# vfd_drive.net
KiCad netlist of a schematic drawn in EAGLE
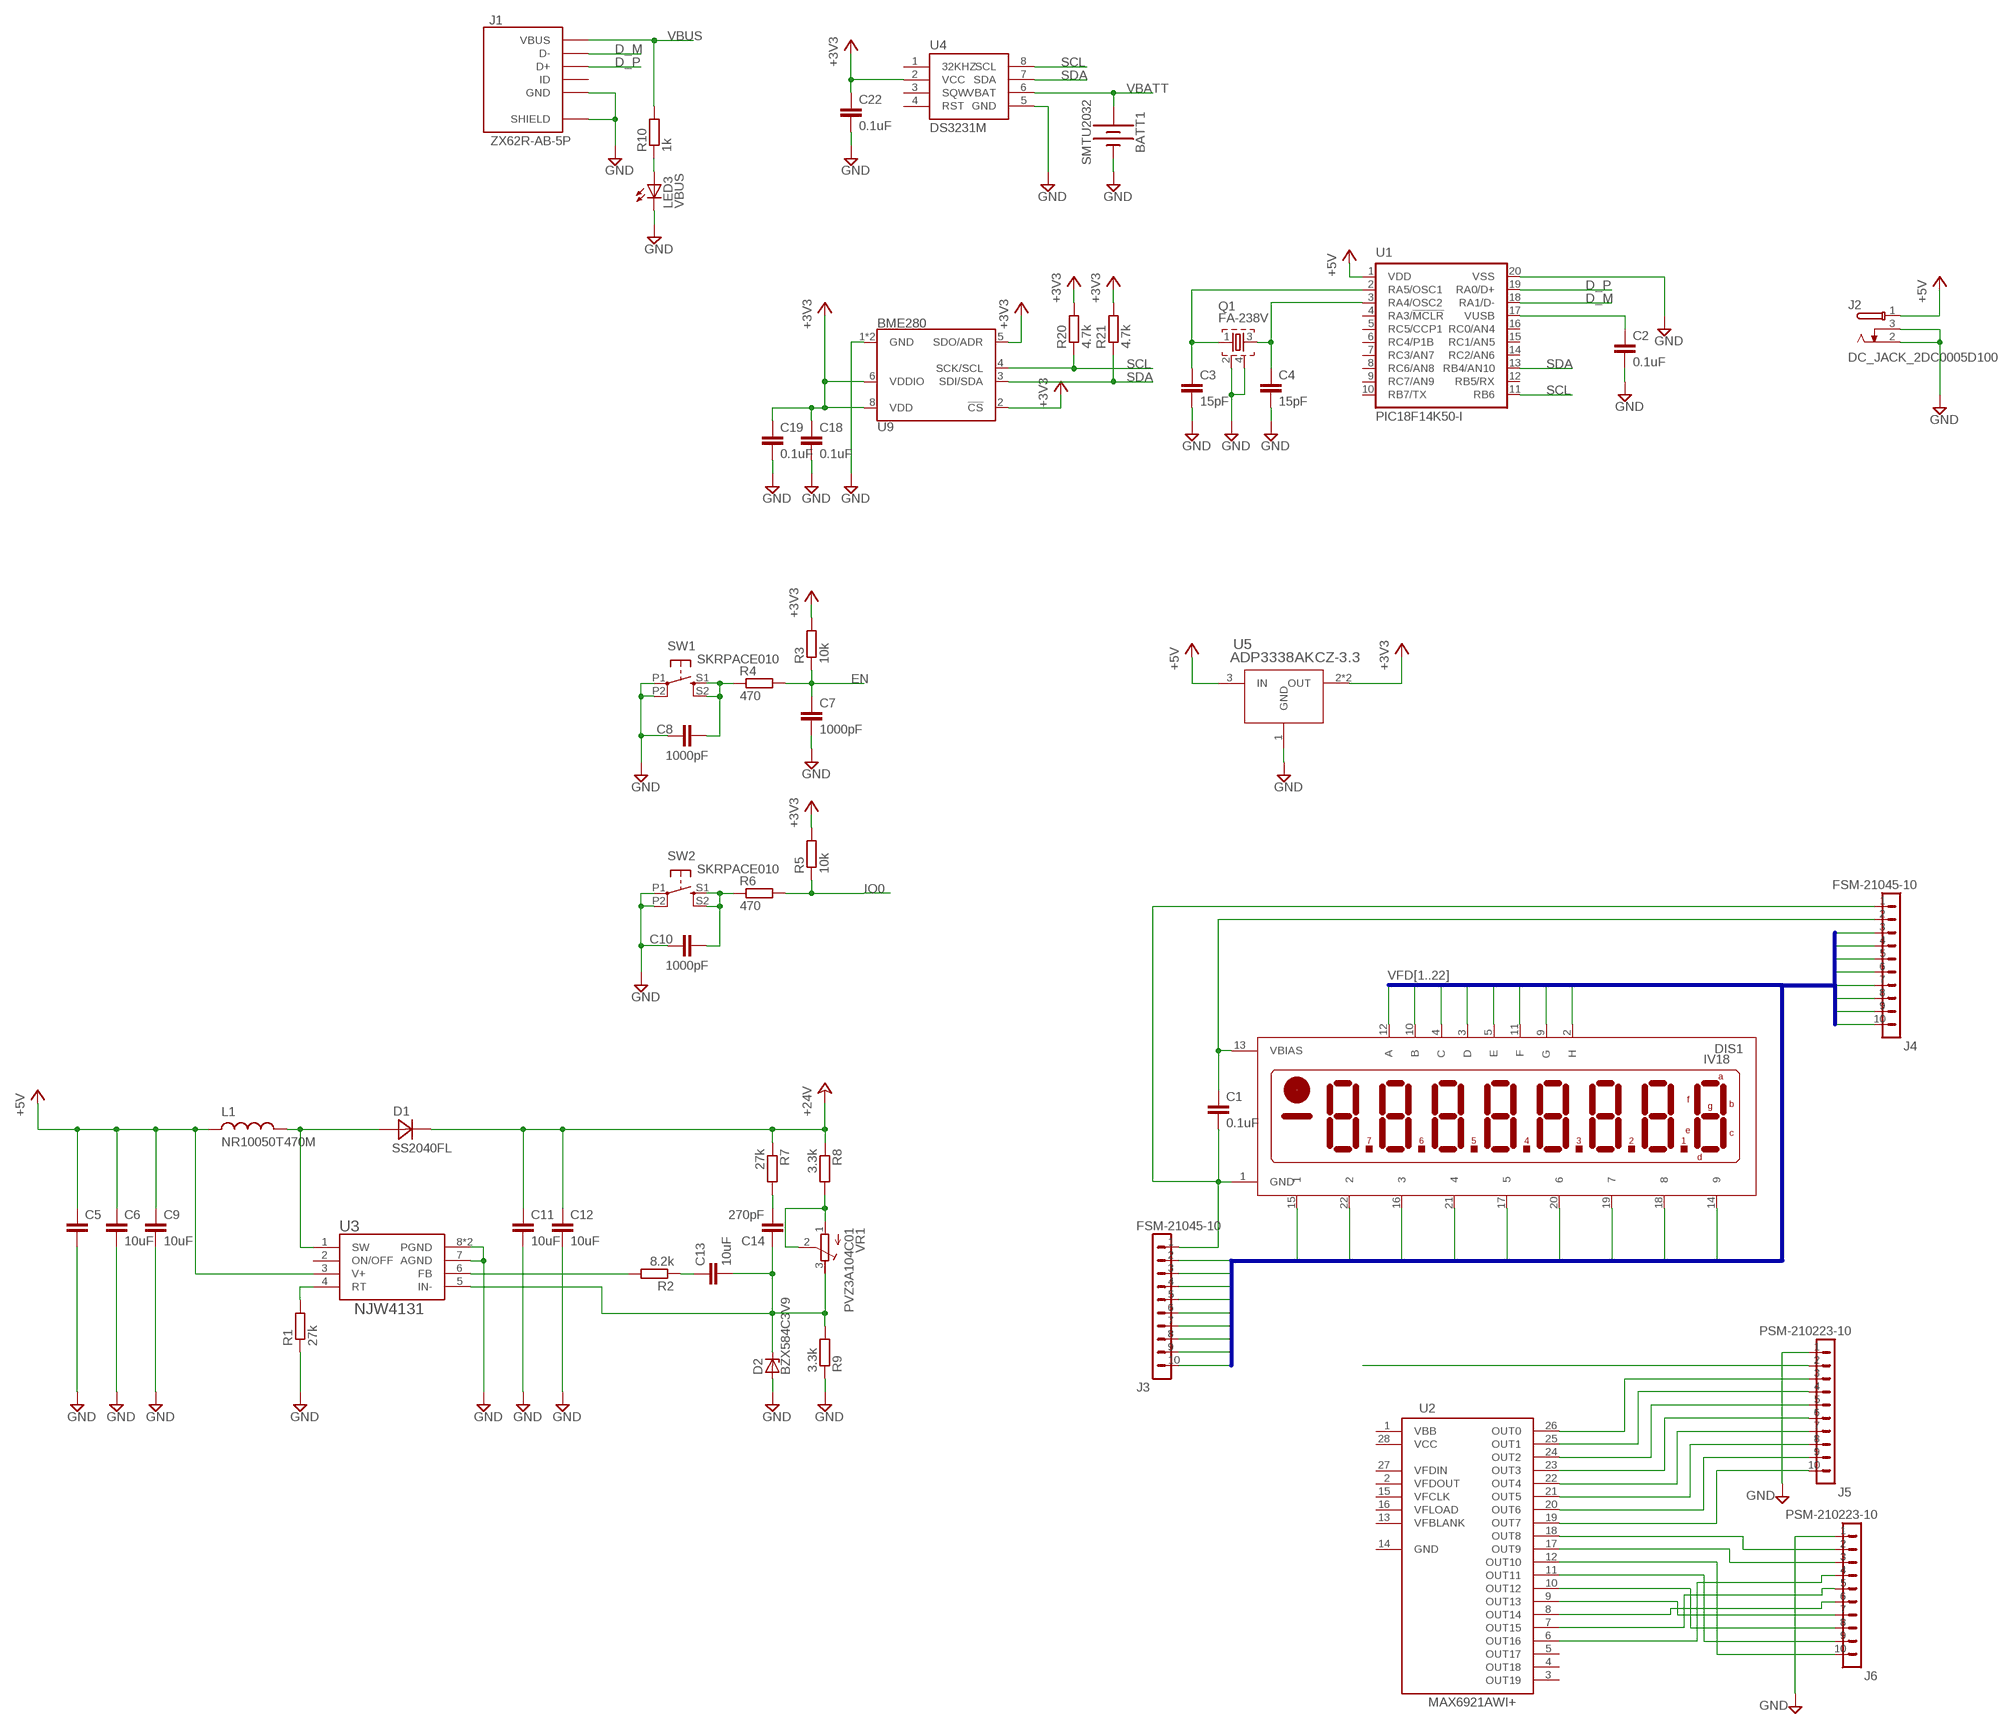
[diagram p0: schematic, sheet 1]

(export (version "E")
  (design (tool "Eeschema 10.0.6"))
  (components
    (comp (ref "BATT1")
      (value "SMTU2032")
      (footprint "eagle-import:SMTU2032")
      (libsource (lib "eagle-import") (part "SMTU2032"))
    )
    (comp (ref "C1")
      (value "0.1uF")
      (footprint "eagle-import:C0603")
      (libsource (lib "eagle-import") (part "C-EUC0603"))
    )
    (comp (ref "C2")
      (value "0.1uF")
      (footprint "eagle-import:C0603")
      (libsource (lib "eagle-import") (part "C-EUC0603"))
    )
    (comp (ref "C3")
      (value "15pF")
      (footprint "eagle-import:C0603")
      (libsource (lib "eagle-import") (part "C-EUC0603"))
    )
    (comp (ref "C4")
      (value "15pF")
      (footprint "eagle-import:C0603")
      (libsource (lib "eagle-import") (part "C-EUC0603"))
    )
    (comp (ref "C5")
      (value "C-EUC3225")
      (footprint "eagle-import:C3225")
      (libsource (lib "eagle-import") (part "C-EUC3225"))
    )
    (comp (ref "C6")
      (value "10uF")
      (footprint "eagle-import:C0603")
      (libsource (lib "eagle-import") (part "C-EUC0603"))
    )
    (comp (ref "C7")
      (value "1000pF")
      (footprint "eagle-import:C0603")
      (libsource (lib "eagle-import") (part "C-EUC0603"))
    )
    (comp (ref "C8")
      (value "1000pF")
      (footprint "eagle-import:C0603")
      (libsource (lib "eagle-import") (part "C-EUC0603"))
    )
    (comp (ref "C9")
      (value "10uF")
      (footprint "eagle-import:C0603")
      (libsource (lib "eagle-import") (part "C-EUC0603"))
    )
    (comp (ref "C10")
      (value "1000pF")
      (footprint "eagle-import:C0603")
      (libsource (lib "eagle-import") (part "C-EUC0603"))
    )
    (comp (ref "C11")
      (value "10uF")
      (footprint "eagle-import:C3216")
      (libsource (lib "eagle-import") (part "C-EUC3216"))
    )
    (comp (ref "C12")
      (value "10uF")
      (footprint "eagle-import:C3216")
      (libsource (lib "eagle-import") (part "C-EUC3216"))
    )
    (comp (ref "C13")
      (value "10uF")
      (footprint "eagle-import:C0603")
      (libsource (lib "eagle-import") (part "C-EUC0603"))
    )
    (comp (ref "C14")
      (value "270pF")
      (footprint "eagle-import:C0603")
      (libsource (lib "eagle-import") (part "C-EUC0603"))
    )
    (comp (ref "C18")
      (value "0.1uF")
      (footprint "eagle-import:C0603")
      (libsource (lib "eagle-import") (part "C-EUC0603"))
    )
    (comp (ref "C19")
      (value "0.1uF")
      (footprint "eagle-import:C0603")
      (libsource (lib "eagle-import") (part "C-EUC0603"))
    )
    (comp (ref "C22")
      (value "0.1uF")
      (footprint "eagle-import:C0603")
      (libsource (lib "eagle-import") (part "C-EUC0603"))
    )
    (comp (ref "D1")
      (value "SS2040FL")
      (footprint "eagle-import:SOD-123FL")
      (libsource (lib "eagle-import") (part "SS2040FL"))
    )
    (comp (ref "D2")
      (value "BZX584C3V9")
      (footprint "eagle-import:SOD-523")
      (libsource (lib "eagle-import") (part "BZX584C3V9"))
    )
    (comp (ref "DIS1")
      (value "IV18")
      (footprint "eagle-import:IV18")
      (libsource (lib "eagle-import") (part "IV18"))
    )
    (comp (ref "J1")
      (value "ZX62R-AB-5P")
      (footprint "eagle-import:ZX62R-B-5PA")
      (libsource (lib "eagle-import") (part "ZX62R-AB-5P"))
    )
    (comp (ref "J2")
      (value "DC_JACK_2DC0005D100")
      (footprint "eagle-import:DC_JACK_2DC0005D100")
      (libsource (lib "eagle-import") (part "DC_JACK_2DC0005D100"))
    )
    (comp (ref "J3")
      (value "FSM-21045-10")
      (footprint "eagle-import:FSM-21045-10")
      (libsource (lib "eagle-import") (part "FSM-21045-10"))
    )
    (comp (ref "J4")
      (value "FSM-21045-10")
      (footprint "eagle-import:FSM-21045-10")
      (libsource (lib "eagle-import") (part "FSM-21045-10"))
    )
    (comp (ref "J5")
      (value "PSM-210223-10")
      (footprint "eagle-import:PSM-210223-10")
      (libsource (lib "eagle-import") (part "PSM-210223-10"))
    )
    (comp (ref "J6")
      (value "PSM-210223-10")
      (footprint "eagle-import:PSM-210223-10")
      (libsource (lib "eagle-import") (part "PSM-210223-10"))
    )
    (comp (ref "L1")
      (value "NR10050T470M")
      (footprint "eagle-import:NR10050T100M")
      (libsource (lib "eagle-import") (part "NR10050T470M"))
    )
    (comp (ref "LED3")
      (value "VBUS")
      (footprint "eagle-import:CHIPLED_0603")
      (libsource (lib "eagle-import") (part "LEDCHIPLED_0603"))
    )
    (comp (ref "Q1")
      (value "FA-238V")
      (footprint "eagle-import:FA238-V")
      (libsource (lib "eagle-import") (part "FA-238V"))
    )
    (comp (ref "R1")
      (value "27k")
      (footprint "eagle-import:R0603")
      (libsource (lib "eagle-import") (part "R-EU_R0603"))
    )
    (comp (ref "R2")
      (value "8.2k")
      (footprint "eagle-import:R0603")
      (libsource (lib "eagle-import") (part "R-EU_R0603"))
    )
    (comp (ref "R3")
      (value "10k")
      (footprint "eagle-import:R0603")
      (libsource (lib "eagle-import") (part "R-EU_R0603"))
    )
    (comp (ref "R4")
      (value "470")
      (footprint "eagle-import:R0603")
      (libsource (lib "eagle-import") (part "R-EU_R0603"))
    )
    (comp (ref "R5")
      (value "10k")
      (footprint "eagle-import:R0603")
      (libsource (lib "eagle-import") (part "R-EU_R0603"))
    )
    (comp (ref "R6")
      (value "470")
      (footprint "eagle-import:R0603")
      (libsource (lib "eagle-import") (part "R-EU_R0603"))
    )
    (comp (ref "R7")
      (value "27k")
      (footprint "eagle-import:R0603")
      (libsource (lib "eagle-import") (part "R-EU_R0603"))
    )
    (comp (ref "R8")
      (value "3.3k")
      (footprint "eagle-import:R0603")
      (libsource (lib "eagle-import") (part "R-EU_R0603"))
    )
    (comp (ref "R9")
      (value "3.3k")
      (footprint "eagle-import:R0603")
      (libsource (lib "eagle-import") (part "R-EU_R0603"))
    )
    (comp (ref "R10")
      (value "1k")
      (footprint "eagle-import:R0603")
      (libsource (lib "eagle-import") (part "R-EU_R0603"))
    )
    (comp (ref "R20")
      (value "4.7k")
      (footprint "eagle-import:R0603")
      (libsource (lib "eagle-import") (part "R-EU_R0603"))
    )
    (comp (ref "R21")
      (value "4.7k")
      (footprint "eagle-import:R0603")
      (libsource (lib "eagle-import") (part "R-EU_R0603"))
    )
    (comp (ref "SW1")
      (value "SKRPACE010")
      (footprint "eagle-import:SKRPACE010")
      (libsource (lib "eagle-import") (part "SKRPACE010"))
    )
    (comp (ref "SW2")
      (value "SKRPACE010")
      (footprint "eagle-import:SKRPACE010")
      (libsource (lib "eagle-import") (part "SKRPACE010"))
    )
    (comp (ref "U1")
      (value "PIC18F14K50-I")
      (footprint "eagle-import:SSOP20")
      (libsource (lib "eagle-import") (part "PIC18F14K50-I"))
    )
    (comp (ref "U2")
      (value "MAX6921AWI+")
      (footprint "eagle-import:SOIC-28-MI")
      (libsource (lib "eagle-import") (part "MAX6921AWI+"))
    )
    (comp (ref "U3")
      (value "NJW4131")
      (footprint "eagle-import:HSOP8")
      (libsource (lib "eagle-import") (part "NJW4131"))
    )
    (comp (ref "U4")
      (value "DS3231M")
      (footprint "eagle-import:SO08")
      (libsource (lib "eagle-import") (part "DS3231M"))
    )
    (comp (ref "U5")
      (value "ADP3338AKCZ-3.3")
      (footprint "eagle-import:SOT233")
      (libsource (lib "eagle-import") (part "ADP3338AKCZ-3.3"))
    )
    (comp (ref "U9")
      (value "BME280")
      (footprint "eagle-import:LGA-8-2.5X2.5")
      (libsource (lib "eagle-import") (part "BME280"))
    )
    (comp (ref "VR1")
      (value "PVZ3A104C01")
      (footprint "eagle-import:PVZ3A")
      (libsource (lib "eagle-import") (part "PVZ3A104C01"))
    )
  )
  (nets
    (net (code "6") (name "+3V3") (class "Default")
      (node (ref "C18") (pin "1") (pinfunction "1_1") (pintype "passive"))
      (node (ref "C19") (pin "1") (pinfunction "1_1") (pintype "passive"))
      (node (ref "C22") (pin "1") (pinfunction "1_1") (pintype "passive"))
      (node (ref "R20") (pin "2") (pinfunction "2_2") (pintype "passive"))
      (node (ref "R21") (pin "2") (pinfunction "2_2") (pintype "passive"))
      (node (ref "R3") (pin "2") (pinfunction "2_2") (pintype "passive"))
      (node (ref "R5") (pin "2") (pinfunction "2_2") (pintype "passive"))
      (node (ref "U4") (pin "2") (pinfunction "VCC_2") (pintype "power_in"))
      (node (ref "U5") (pin "2") (pinfunction "OUT_2") (pintype "passive"))
      (node (ref "U5") (pin "4") (pinfunction "OUT_4") (pintype "passive"))
      (node (ref "U9") (pin "2") (pinfunction "~{CS}_2") (pintype "bidirectional"))
      (node (ref "U9") (pin "5") (pinfunction "SDO/ADR_5") (pintype "bidirectional"))
      (node (ref "U9") (pin "6") (pinfunction "VDDIO_6") (pintype "bidirectional"))
      (node (ref "U9") (pin "8") (pinfunction "VDD_8") (pintype "bidirectional"))
    )
    (net (code "7") (name "+5V") (class "Default")
      (node (ref "C5") (pin "1") (pinfunction "1_1") (pintype "passive"))
      (node (ref "C6") (pin "1") (pinfunction "1_1") (pintype "passive"))
      (node (ref "C9") (pin "1") (pinfunction "1_1") (pintype "passive"))
      (node (ref "J2") (pin "1") (pinfunction "1_1") (pintype "passive"))
      (node (ref "L1") (pin "P$1") (pinfunction "1_P$1") (pintype "passive"))
      (node (ref "U1") (pin "1") (pinfunction "VDD_1") (pintype "power_in"))
      (node (ref "U3") (pin "3") (pinfunction "V+_3") (pintype "bidirectional"))
      (node (ref "U5") (pin "3") (pinfunction "IN_3") (pintype "passive"))
    )
    (net (code "8") (name "+24V") (class "Default")
      (node (ref "C11") (pin "1") (pinfunction "1_1") (pintype "passive"))
      (node (ref "C12") (pin "1") (pinfunction "1_1") (pintype "passive"))
      (node (ref "D1") (pin "K") (pinfunction "C_K") (pintype "passive"))
      (node (ref "R7") (pin "1") (pinfunction "1_1") (pintype "passive"))
      (node (ref "R8") (pin "1") (pinfunction "1_1") (pintype "passive"))
    )
    (net (code "9") (name "/D_M") (class "Default")
      (node (ref "J1") (pin "D-") (pinfunction "D-_D-") (pintype "bidirectional"))
      (node (ref "U1") (pin "18") (pinfunction "RA1/D-_18") (pintype "bidirectional"))
    )
    (net (code "10") (name "/D_P") (class "Default")
      (node (ref "J1") (pin "D+") (pinfunction "D+_D+") (pintype "bidirectional"))
      (node (ref "U1") (pin "19") (pinfunction "RA0/D+_19") (pintype "bidirectional"))
    )
    (net (code "11") (name "/EN") (class "Default")
      (node (ref "C7") (pin "1") (pinfunction "1_1") (pintype "passive"))
      (node (ref "R3") (pin "1") (pinfunction "1_1") (pintype "passive"))
      (node (ref "R4") (pin "2") (pinfunction "2_2") (pintype "passive"))
    )
    (net (code "12") (name "/IO0") (class "Default")
      (node (ref "R5") (pin "1") (pinfunction "1_1") (pintype "passive"))
      (node (ref "R6") (pin "2") (pinfunction "2_2") (pintype "passive"))
    )
    (net (code "13") (name "/SCL") (class "Default")
      (node (ref "R20") (pin "1") (pinfunction "1_1") (pintype "passive"))
      (node (ref "U1") (pin "11") (pinfunction "RB6_11") (pintype "bidirectional"))
      (node (ref "U4") (pin "8") (pinfunction "SCL_8") (pintype "bidirectional"))
      (node (ref "U9") (pin "4") (pinfunction "SCK/SCL_4") (pintype "bidirectional"))
    )
    (net (code "14") (name "/SDA") (class "Default")
      (node (ref "R21") (pin "1") (pinfunction "1_1") (pintype "passive"))
      (node (ref "U1") (pin "13") (pinfunction "RB4/AN10_13") (pintype "bidirectional"))
      (node (ref "U4") (pin "7") (pinfunction "SDA_7") (pintype "bidirectional"))
      (node (ref "U9") (pin "3") (pinfunction "SDI/SDA_3") (pintype "bidirectional"))
    )
    (net (code "15") (name "/VBATT") (class "Default")
      (node (ref "BATT1") (pin "P") (pinfunction "+_P") (pintype "power_in"))
      (node (ref "U4") (pin "6") (pinfunction "VBAT_6") (pintype "power_in"))
    )
    (net (code "16") (name "/VBUS") (class "Default")
      (node (ref "J1") (pin "VCC") (pinfunction "VBUS_VCC") (pintype "bidirectional"))
      (node (ref "R10") (pin "2") (pinfunction "2_2") (pintype "passive"))
    )
    (net (code "17") (name "/VFD2") (class "Default")
      (node (ref "DIS1") (pin "2") (pinfunction "H_2") (pintype "passive"))
      (node (ref "J3") (pin "5") (pinfunction "5_5") (pintype "bidirectional"))
    )
    (net (code "18") (name "/VFD3") (class "Default")
      (node (ref "DIS1") (pin "3") (pinfunction "D_3") (pintype "passive"))
      (node (ref "J3") (pin "4") (pinfunction "4_4") (pintype "bidirectional"))
    )
    (net (code "19") (name "/VFD4") (class "Default")
      (node (ref "DIS1") (pin "4") (pinfunction "C_4") (pintype "passive"))
      (node (ref "J3") (pin "3") (pinfunction "3_3") (pintype "bidirectional"))
    )
    (net (code "20") (name "/VFD5") (class "Default")
      (node (ref "DIS1") (pin "5") (pinfunction "E_5") (pintype "passive"))
      (node (ref "J3") (pin "2") (pinfunction "2_2") (pintype "bidirectional"))
    )
    (net (code "21") (name "/VFD9") (class "Default")
      (node (ref "DIS1") (pin "9") (pinfunction "G_9") (pintype "passive"))
      (node (ref "J4") (pin "3") (pinfunction "3_3") (pintype "bidirectional"))
    )
    (net (code "22") (name "/VFD10") (class "Default")
      (node (ref "DIS1") (pin "10") (pinfunction "B_10") (pintype "passive"))
      (node (ref "J4") (pin "4") (pinfunction "4_4") (pintype "bidirectional"))
    )
    (net (code "23") (name "/VFD11") (class "Default")
      (node (ref "DIS1") (pin "11") (pinfunction "F_11") (pintype "passive"))
      (node (ref "J4") (pin "5") (pinfunction "5_5") (pintype "bidirectional"))
    )
    (net (code "24") (name "/VFD12") (class "Default")
      (node (ref "DIS1") (pin "12") (pinfunction "A_12") (pintype "passive"))
      (node (ref "J4") (pin "6") (pinfunction "6_6") (pintype "bidirectional"))
    )
    (net (code "25") (name "/VFD14") (class "Default")
      (node (ref "DIS1") (pin "14") (pinfunction "9_14") (pintype "passive"))
      (node (ref "J4") (pin "7") (pinfunction "7_7") (pintype "bidirectional"))
    )
    (net (code "26") (name "/VFD15") (class "Default")
      (node (ref "DIS1") (pin "15") (pinfunction "1_15") (pintype "passive"))
      (node (ref "J4") (pin "8") (pinfunction "8_8") (pintype "bidirectional"))
    )
    (net (code "27") (name "/VFD16") (class "Default")
      (node (ref "DIS1") (pin "16") (pinfunction "3_16") (pintype "passive"))
      (node (ref "J4") (pin "9") (pinfunction "9_9") (pintype "bidirectional"))
    )
    (net (code "28") (name "/VFD17") (class "Default")
      (node (ref "DIS1") (pin "17") (pinfunction "5_17") (pintype "passive"))
      (node (ref "J4") (pin "10") (pinfunction "10_10") (pintype "bidirectional"))
    )
    (net (code "29") (name "/VFD18") (class "Default")
      (node (ref "DIS1") (pin "18") (pinfunction "8_18") (pintype "passive"))
      (node (ref "J3") (pin "10") (pinfunction "10_10") (pintype "bidirectional"))
    )
    (net (code "30") (name "/VFD19") (class "Default")
      (node (ref "DIS1") (pin "19") (pinfunction "7_19") (pintype "passive"))
      (node (ref "J3") (pin "9") (pinfunction "9_9") (pintype "bidirectional"))
    )
    (net (code "31") (name "/VFD20") (class "Default")
      (node (ref "DIS1") (pin "20") (pinfunction "6_20") (pintype "passive"))
      (node (ref "J3") (pin "8") (pinfunction "8_8") (pintype "bidirectional"))
    )
    (net (code "32") (name "/VFD21") (class "Default")
      (node (ref "DIS1") (pin "21") (pinfunction "4_21") (pintype "passive"))
      (node (ref "J3") (pin "7") (pinfunction "7_7") (pintype "bidirectional"))
    )
    (net (code "33") (name "/VFD22") (class "Default")
      (node (ref "DIS1") (pin "22") (pinfunction "2_22") (pintype "passive"))
      (node (ref "J3") (pin "6") (pinfunction "6_6") (pintype "bidirectional"))
    )
    (net (code "35") (name "GND") (class "Default")
      (node (ref "BATT1") (pin "N") (pinfunction "-_N") (pintype "power_in"))
      (node (ref "C1") (pin "2") (pinfunction "2_2") (pintype "passive"))
      (node (ref "C10") (pin "1") (pinfunction "1_1") (pintype "passive"))
      (node (ref "C11") (pin "2") (pinfunction "2_2") (pintype "passive"))
      (node (ref "C12") (pin "2") (pinfunction "2_2") (pintype "passive"))
      (node (ref "C18") (pin "2") (pinfunction "2_2") (pintype "passive"))
      (node (ref "C19") (pin "2") (pinfunction "2_2") (pintype "passive"))
      (node (ref "C2") (pin "2") (pinfunction "2_2") (pintype "passive"))
      (node (ref "C22") (pin "2") (pinfunction "2_2") (pintype "passive"))
      (node (ref "C3") (pin "2") (pinfunction "2_2") (pintype "passive"))
      (node (ref "C4") (pin "2") (pinfunction "2_2") (pintype "passive"))
      (node (ref "C5") (pin "2") (pinfunction "2_2") (pintype "passive"))
      (node (ref "C6") (pin "2") (pinfunction "2_2") (pintype "passive"))
      (node (ref "C7") (pin "2") (pinfunction "2_2") (pintype "passive"))
      (node (ref "C8") (pin "1") (pinfunction "1_1") (pintype "passive"))
      (node (ref "C9") (pin "2") (pinfunction "2_2") (pintype "passive"))
      (node (ref "D2") (pin "A") (pinfunction "A_A") (pintype "passive"))
      (node (ref "DIS1") (pin "1") (pinfunction "GND_1") (pintype "power_in"))
      (node (ref "J1") (pin "GND") (pinfunction "GND_GND") (pintype "bidirectional"))
      (node (ref "J1") (pin "SHIELD@1") (pinfunction "SHIELD_SHIELD@1") (pintype "bidirectional"))
      (node (ref "J1") (pin "SHIELD@2") (pinfunction "SHIELD_SHIELD@2") (pintype "bidirectional"))
      (node (ref "J1") (pin "SHIELD@3") (pinfunction "SHIELD_SHIELD@3") (pintype "bidirectional"))
      (node (ref "J1") (pin "SHIELD@4") (pinfunction "SHIELD_SHIELD@4") (pintype "bidirectional"))
      (node (ref "J2") (pin "2") (pinfunction "2_2") (pintype "passive"))
      (node (ref "J2") (pin "3") (pinfunction "3_3") (pintype "passive"))
      (node (ref "J3") (pin "1") (pinfunction "1_1") (pintype "bidirectional"))
      (node (ref "J4") (pin "1") (pinfunction "1_1") (pintype "bidirectional"))
      (node (ref "J5") (pin "1") (pinfunction "1_1") (pintype "bidirectional"))
      (node (ref "J6") (pin "1") (pinfunction "1_1") (pintype "bidirectional"))
      (node (ref "LED3") (pin "C") (pinfunction "C_C") (pintype "passive"))
      (node (ref "Q1") (pin "2") (pinfunction "2_2") (pintype "passive"))
      (node (ref "Q1") (pin "4") (pinfunction "4_4") (pintype "passive"))
      (node (ref "R1") (pin "1") (pinfunction "1_1") (pintype "passive"))
      (node (ref "R9") (pin "1") (pinfunction "1_1") (pintype "passive"))
      (node (ref "SW1") (pin "P1") (pinfunction "P_P1") (pintype "passive"))
      (node (ref "SW1") (pin "P2") (pinfunction "P1_P2") (pintype "passive"))
      (node (ref "SW2") (pin "P1") (pinfunction "P_P1") (pintype "passive"))
      (node (ref "SW2") (pin "P2") (pinfunction "P1_P2") (pintype "passive"))
      (node (ref "U1") (pin "20") (pinfunction "VSS_20") (pintype "power_in"))
      (node (ref "U3") (pin "7") (pinfunction "AGND_7") (pintype "bidirectional"))
      (node (ref "U3") (pin "8") (pinfunction "PGND_8") (pintype "bidirectional"))
      (node (ref "U3") (pin "PAD") (pinfunction "PGND_PAD") (pintype "bidirectional"))
      (node (ref "U4") (pin "5") (pinfunction "GND_5") (pintype "power_in"))
      (node (ref "U5") (pin "1") (pinfunction "GND_1") (pintype "passive"))
      (node (ref "U9") (pin "1") (pinfunction "GND_1") (pintype "bidirectional"))
      (node (ref "U9") (pin "7") (pinfunction "GND_7") (pintype "bidirectional"))
    )
    (net (code "36") (name "Net-(C13-Pad1)") (class "Default")
      (node (ref "C13") (pin "1") (pinfunction "1_1") (pintype "passive"))
      (node (ref "R2") (pin "1") (pinfunction "1_1") (pintype "passive"))
    )
    (net (code "37") (name "Net-(C14-Pad2)") (class "Default")
      (node (ref "C14") (pin "2") (pinfunction "2_2") (pintype "passive"))
      (node (ref "R7") (pin "2") (pinfunction "2_2") (pintype "passive"))
    )
    (net (code "38") (name "Net-(D2-C)") (class "Default")
      (node (ref "C13") (pin "2") (pinfunction "2_2") (pintype "passive"))
      (node (ref "C14") (pin "1") (pinfunction "1_1") (pintype "passive"))
      (node (ref "D2") (pin "K") (pinfunction "C_K") (pintype "passive"))
      (node (ref "R9") (pin "2") (pinfunction "2_2") (pintype "passive"))
      (node (ref "U3") (pin "5") (pinfunction "IN-_5") (pintype "bidirectional"))
      (node (ref "VR1") (pin "3") (pinfunction "A_3") (pintype "passive"))
    )
    (net (code "39") (name "Net-(DIS1-VBIAS)") (class "Default")
      (node (ref "C1") (pin "1") (pinfunction "1_1") (pintype "passive"))
      (node (ref "DIS1") (pin "13") (pinfunction "VBIAS_13") (pintype "power_in"))
      (node (ref "J4") (pin "2") (pinfunction "2_2") (pintype "bidirectional"))
    )
    (net (code "40") (name "Net-(L1-2)") (class "Default")
      (node (ref "D1") (pin "A") (pinfunction "A_A") (pintype "passive"))
      (node (ref "L1") (pin "P$2") (pinfunction "2_P$2") (pintype "passive"))
      (node (ref "U3") (pin "1") (pinfunction "SW_1") (pintype "bidirectional"))
    )
    (net (code "41") (name "Net-(LED3-PadA)") (class "Default")
      (node (ref "LED3") (pin "A") (pinfunction "A_A") (pintype "passive"))
      (node (ref "R10") (pin "1") (pinfunction "1_1") (pintype "passive"))
    )
    (net (code "42") (name "Net-(SW1-S)") (class "Default")
      (node (ref "C8") (pin "2") (pinfunction "2_2") (pintype "passive"))
      (node (ref "R4") (pin "1") (pinfunction "1_1") (pintype "passive"))
      (node (ref "SW1") (pin "S1") (pinfunction "S_S1") (pintype "passive"))
      (node (ref "SW1") (pin "S2") (pinfunction "S1_S2") (pintype "passive"))
    )
    (net (code "43") (name "Net-(SW2-S)") (class "Default")
      (node (ref "C10") (pin "2") (pinfunction "2_2") (pintype "passive"))
      (node (ref "R6") (pin "1") (pinfunction "1_1") (pintype "passive"))
      (node (ref "SW2") (pin "S1") (pinfunction "S_S1") (pintype "passive"))
      (node (ref "SW2") (pin "S2") (pinfunction "S1_S2") (pintype "passive"))
    )
    (net (code "44") (name "Net-(U1-RA4{slash}OSC2)") (class "Default")
      (node (ref "C4") (pin "1") (pinfunction "1_1") (pintype "passive"))
      (node (ref "Q1") (pin "3") (pinfunction "3_3") (pintype "passive"))
      (node (ref "U1") (pin "3") (pinfunction "RA4/OSC2_3") (pintype "bidirectional"))
    )
    (net (code "45") (name "Net-(U1-RA5{slash}OSC1)") (class "Default")
      (node (ref "C3") (pin "1") (pinfunction "1_1") (pintype "passive"))
      (node (ref "Q1") (pin "1") (pinfunction "1_1") (pintype "passive"))
      (node (ref "U1") (pin "2") (pinfunction "RA5/OSC1_2") (pintype "bidirectional"))
    )
    (net (code "46") (name "Net-(U1-VUSB)") (class "Default")
      (node (ref "C2") (pin "1") (pinfunction "1_1") (pintype "passive"))
      (node (ref "U1") (pin "17") (pinfunction "VUSB_17") (pintype "bidirectional"))
    )
    (net (code "47") (name "Net-(U2-OUT0)") (class "Default")
      (node (ref "J5") (pin "3") (pinfunction "3_3") (pintype "bidirectional"))
      (node (ref "U2") (pin "26") (pinfunction "OUT0_26") (pintype "bidirectional"))
    )
    (net (code "48") (name "Net-(U2-OUT1)") (class "Default")
      (node (ref "J5") (pin "4") (pinfunction "4_4") (pintype "bidirectional"))
      (node (ref "U2") (pin "25") (pinfunction "OUT1_25") (pintype "bidirectional"))
    )
    (net (code "49") (name "Net-(U2-OUT2)") (class "Default")
      (node (ref "J5") (pin "5") (pinfunction "5_5") (pintype "bidirectional"))
      (node (ref "U2") (pin "24") (pinfunction "OUT2_24") (pintype "bidirectional"))
    )
    (net (code "50") (name "Net-(U2-OUT3)") (class "Default")
      (node (ref "J5") (pin "6") (pinfunction "6_6") (pintype "bidirectional"))
      (node (ref "U2") (pin "23") (pinfunction "OUT3_23") (pintype "bidirectional"))
    )
    (net (code "51") (name "Net-(U2-OUT4)") (class "Default")
      (node (ref "J5") (pin "7") (pinfunction "7_7") (pintype "bidirectional"))
      (node (ref "U2") (pin "22") (pinfunction "OUT4_22") (pintype "bidirectional"))
    )
    (net (code "52") (name "Net-(U2-OUT5)") (class "Default")
      (node (ref "J5") (pin "8") (pinfunction "8_8") (pintype "bidirectional"))
      (node (ref "U2") (pin "21") (pinfunction "OUT5_21") (pintype "bidirectional"))
    )
    (net (code "53") (name "Net-(U2-OUT6)") (class "Default")
      (node (ref "J5") (pin "9") (pinfunction "9_9") (pintype "bidirectional"))
      (node (ref "U2") (pin "20") (pinfunction "OUT6_20") (pintype "bidirectional"))
    )
    (net (code "54") (name "Net-(U2-OUT7)") (class "Default")
      (node (ref "J5") (pin "10") (pinfunction "10_10") (pintype "bidirectional"))
      (node (ref "U2") (pin "19") (pinfunction "OUT7_19") (pintype "bidirectional"))
    )
    (net (code "55") (name "Net-(U2-OUT8)") (class "Default")
      (node (ref "J6") (pin "2") (pinfunction "2_2") (pintype "bidirectional"))
      (node (ref "U2") (pin "18") (pinfunction "OUT8_18") (pintype "bidirectional"))
    )
    (net (code "56") (name "Net-(U2-OUT9)") (class "Default")
      (node (ref "J6") (pin "3") (pinfunction "3_3") (pintype "bidirectional"))
      (node (ref "U2") (pin "17") (pinfunction "OUT9_17") (pintype "bidirectional"))
    )
    (net (code "57") (name "Net-(U2-OUT10)") (class "Default")
      (node (ref "J6") (pin "10") (pinfunction "10_10") (pintype "bidirectional"))
      (node (ref "U2") (pin "12") (pinfunction "OUT10_12") (pintype "bidirectional"))
    )
    (net (code "58") (name "Net-(U2-OUT11)") (class "Default")
      (node (ref "J6") (pin "9") (pinfunction "9_9") (pintype "bidirectional"))
      (node (ref "U2") (pin "11") (pinfunction "OUT11_11") (pintype "bidirectional"))
    )
    (net (code "59") (name "Net-(U2-OUT12)") (class "Default")
      (node (ref "J6") (pin "8") (pinfunction "8_8") (pintype "bidirectional"))
      (node (ref "U2") (pin "10") (pinfunction "OUT12_10") (pintype "bidirectional"))
    )
    (net (code "60") (name "Net-(U2-OUT13)") (class "Default")
      (node (ref "J6") (pin "7") (pinfunction "7_7") (pintype "bidirectional"))
      (node (ref "U2") (pin "9") (pinfunction "OUT13_9") (pintype "bidirectional"))
    )
    (net (code "61") (name "Net-(U2-OUT14)") (class "Default")
      (node (ref "J6") (pin "6") (pinfunction "6_6") (pintype "bidirectional"))
      (node (ref "U2") (pin "8") (pinfunction "OUT14_8") (pintype "bidirectional"))
    )
    (net (code "62") (name "Net-(U2-OUT15)") (class "Default")
      (node (ref "J6") (pin "5") (pinfunction "5_5") (pintype "bidirectional"))
      (node (ref "U2") (pin "7") (pinfunction "OUT15_7") (pintype "bidirectional"))
    )
    (net (code "63") (name "Net-(U2-OUT16)") (class "Default")
      (node (ref "J6") (pin "4") (pinfunction "4_4") (pintype "bidirectional"))
      (node (ref "U2") (pin "6") (pinfunction "OUT16_6") (pintype "bidirectional"))
    )
    (net (code "64") (name "Net-(U3-FB)") (class "Default")
      (node (ref "R2") (pin "2") (pinfunction "2_2") (pintype "passive"))
      (node (ref "U3") (pin "6") (pinfunction "FB_6") (pintype "bidirectional"))
    )
    (net (code "65") (name "Net-(U3-RT)") (class "Default")
      (node (ref "R1") (pin "2") (pinfunction "2_2") (pintype "passive"))
      (node (ref "U3") (pin "4") (pinfunction "RT_4") (pintype "bidirectional"))
    )
    (net (code "66") (name "Net-(VR1-E)") (class "Default")
      (node (ref "R8") (pin "2") (pinfunction "2_2") (pintype "passive"))
      (node (ref "VR1") (pin "1") (pinfunction "E_1") (pintype "passive"))
      (node (ref "VR1") (pin "2") (pinfunction "S_2") (pintype "passive"))
    )
    (net (code "67") (name "unconnected-(J1-PadID)") (class "Default")
      (node (ref "J1") (pin "ID") (pinfunction "ID_ID") (pintype "bidirectional"))
    )
    (net (code "68") (name "unconnected-(J5-Pad2)") (class "Default")
      (node (ref "J5") (pin "2") (pinfunction "2_2") (pintype "bidirectional"))
    )
    (net (code "69") (name "unconnected-(U1-RA3{slash}~{MCLR}-Pad4)") (class "Default")
      (node (ref "U1") (pin "4") (pinfunction "RA3/~{MCLR}_4") (pintype "bidirectional"))
    )
    (net (code "70") (name "unconnected-(U1-RB5{slash}RX-Pad12)") (class "Default")
      (node (ref "U1") (pin "12") (pinfunction "RB5/RX_12") (pintype "bidirectional"))
    )
    (net (code "71") (name "unconnected-(U1-RB7{slash}TX-Pad10)") (class "Default")
      (node (ref "U1") (pin "10") (pinfunction "RB7/TX_10") (pintype "bidirectional"))
    )
    (net (code "72") (name "unconnected-(U1-RC0{slash}AN4-Pad16)") (class "Default")
      (node (ref "U1") (pin "16") (pinfunction "RC0/AN4_16") (pintype "bidirectional"))
    )
    (net (code "73") (name "unconnected-(U1-RC1{slash}AN5-Pad15)") (class "Default")
      (node (ref "U1") (pin "15") (pinfunction "RC1/AN5_15") (pintype "bidirectional"))
    )
    (net (code "74") (name "unconnected-(U1-RC2{slash}AN6-Pad14)") (class "Default")
      (node (ref "U1") (pin "14") (pinfunction "RC2/AN6_14") (pintype "bidirectional"))
    )
    (net (code "75") (name "unconnected-(U1-RC3{slash}AN7-Pad7)") (class "Default")
      (node (ref "U1") (pin "7") (pinfunction "RC3/AN7_7") (pintype "bidirectional"))
    )
    (net (code "76") (name "unconnected-(U1-RC4{slash}P1B-Pad6)") (class "Default")
      (node (ref "U1") (pin "6") (pinfunction "RC4/P1B_6") (pintype "bidirectional"))
    )
    (net (code "77") (name "unconnected-(U1-RC5{slash}CCP1-Pad5)") (class "Default")
      (node (ref "U1") (pin "5") (pinfunction "RC5/CCP1_5") (pintype "bidirectional"))
    )
    (net (code "78") (name "unconnected-(U1-RC6{slash}AN8-Pad8)") (class "Default")
      (node (ref "U1") (pin "8") (pinfunction "RC6/AN8_8") (pintype "bidirectional"))
    )
    (net (code "79") (name "unconnected-(U1-RC7{slash}AN9-Pad9)") (class "Default")
      (node (ref "U1") (pin "9") (pinfunction "RC7/AN9_9") (pintype "bidirectional"))
    )
    (net (code "80") (name "unconnected-(U2-GND-Pad14)") (class "Default")
      (node (ref "U2") (pin "14") (pinfunction "GND_14") (pintype "bidirectional"))
    )
    (net (code "81") (name "unconnected-(U2-OUT17-Pad5)") (class "Default")
      (node (ref "U2") (pin "5") (pinfunction "OUT17_5") (pintype "bidirectional"))
    )
    (net (code "82") (name "unconnected-(U2-OUT18-Pad4)") (class "Default")
      (node (ref "U2") (pin "4") (pinfunction "OUT18_4") (pintype "bidirectional"))
    )
    (net (code "83") (name "unconnected-(U2-OUT19-Pad3)") (class "Default")
      (node (ref "U2") (pin "3") (pinfunction "OUT19_3") (pintype "bidirectional"))
    )
    (net (code "84") (name "unconnected-(U2-VBB-Pad1)") (class "Default")
      (node (ref "U2") (pin "1") (pinfunction "VBB_1") (pintype "bidirectional"))
    )
    (net (code "85") (name "unconnected-(U2-VCC-Pad28)") (class "Default")
      (node (ref "U2") (pin "28") (pinfunction "VCC_28") (pintype "bidirectional"))
    )
    (net (code "86") (name "unconnected-(U2-VFBLANK-Pad13)") (class "Default")
      (node (ref "U2") (pin "13") (pinfunction "VFBLANK_13") (pintype "bidirectional"))
    )
    (net (code "87") (name "unconnected-(U2-VFCLK-Pad15)") (class "Default")
      (node (ref "U2") (pin "15") (pinfunction "VFCLK_15") (pintype "bidirectional"))
    )
    (net (code "88") (name "unconnected-(U2-VFDIN-Pad27)") (class "Default")
      (node (ref "U2") (pin "27") (pinfunction "VFDIN_27") (pintype "bidirectional"))
    )
    (net (code "89") (name "unconnected-(U2-VFDOUT-Pad2)") (class "Default")
      (node (ref "U2") (pin "2") (pinfunction "VFDOUT_2") (pintype "bidirectional"))
    )
    (net (code "90") (name "unconnected-(U2-VFLOAD-Pad16)") (class "Default")
      (node (ref "U2") (pin "16") (pinfunction "VFLOAD_16") (pintype "bidirectional"))
    )
    (net (code "91") (name "unconnected-(U3-ON{slash}OFF-Pad2)") (class "Default")
      (node (ref "U3") (pin "2") (pinfunction "ON/OFF_2") (pintype "bidirectional"))
    )
    (net (code "92") (name "unconnected-(U4-32KHZ-Pad1)") (class "Default")
      (node (ref "U4") (pin "1") (pinfunction "32KHZ_1") (pintype "output"))
    )
    (net (code "93") (name "unconnected-(U4-RST-Pad4)") (class "Default")
      (node (ref "U4") (pin "4") (pinfunction "RST_4") (pintype "bidirectional"))
    )
    (net (code "94") (name "unconnected-(U4-SQW-Pad3)") (class "Default")
      (node (ref "U4") (pin "3") (pinfunction "SQW_3") (pintype "output"))
    )
  )
)
